# ISO_I2C.net
KiCad netlist of a schematic drawn in Altium Designer
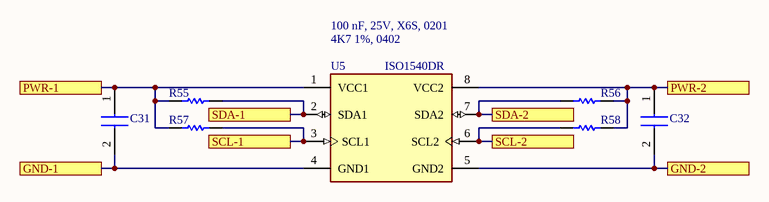
[diagram p0: ISO_I2C.SchDoc]

(export (version "E")
  (design (tool "Eeschema 10.0.6"))
  (components
    (comp (ref "C31")
      (value "100 nF, 25V, X6S, 0201")
      (footprint "SamacSys:CAPC0603X33N")
      (description "Capacitor")
      (fields
        (field (name "MANUFACTURER_PART_NUMBER") "GRM033C81E104KE14D")
        (field (name "MOUSER PART NUMBER") "81-GRM33C81E104KE14D")
      )
      (libsource (lib "*") (part "GRM033C81E104KE14D"))
    )
    (comp (ref "C32")
      (value "100 nF, 25V, X6S, 0201")
      (footprint "SamacSys:CAPC0603X33N")
      (description "Capacitor")
      (fields
        (field (name "MANUFACTURER_PART_NUMBER") "GRM033C81E104KE14D")
        (field (name "MOUSER PART NUMBER") "81-GRM33C81E104KE14D")
      )
      (libsource (lib "*") (part "GRM033C81E104KE14D"))
    )
    (comp (ref "R55")
      (value "4K7 1%, 0402")
      (footprint "RESC1005X40X25LL05T05")
      (description "Chip Resistor, 4.7 KOhm, +/- 1%, 0.1 W, -55 to 155 degC, 0402 (1005 Metric), RoHS, Tape and Reel")
      (fields (field (name "TOLERANCE") "1%") (field (name "PARTNUMBER") "ERJ-2RKF4701X"))
      (libsource (lib "Altium Content Vault") (part "RES-2"))
    )
    (comp (ref "R56")
      (value "4K7 1%, 0402")
      (footprint "RESC1005X40X25LL05T05")
      (description "Chip Resistor, 4.7 KOhm, +/- 1%, 0.1 W, -55 to 155 degC, 0402 (1005 Metric), RoHS, Tape and Reel")
      (fields (field (name "TOLERANCE") "1%") (field (name "PARTNUMBER") "ERJ-2RKF4701X"))
      (libsource (lib "Altium Content Vault") (part "RES-2"))
    )
    (comp (ref "R57")
      (value "4K7 1%, 0402")
      (footprint "RESC1005X40X25LL05T05")
      (description "Chip Resistor, 4.7 KOhm, +/- 1%, 0.1 W, -55 to 155 degC, 0402 (1005 Metric), RoHS, Tape and Reel")
      (fields (field (name "TOLERANCE") "1%") (field (name "PARTNUMBER") "ERJ-2RKF4701X"))
      (libsource (lib "Altium Content Vault") (part "RES-2"))
    )
    (comp (ref "R58")
      (value "4K7 1%, 0402")
      (footprint "RESC1005X40X25LL05T05")
      (description "Chip Resistor, 4.7 KOhm, +/- 1%, 0.1 W, -55 to 155 degC, 0402 (1005 Metric), RoHS, Tape and Reel")
      (fields (field (name "TOLERANCE") "1%") (field (name "PARTNUMBER") "ERJ-2RKF4701X"))
      (libsource (lib "Altium Content Vault") (part "RES-2"))
    )
    (comp (ref "U5")
      (value "ISO1540DR")
      (footprint "FP-D0008A-MFG")
      (description "DGTL ISO 2.5KV 2CH I2C 8SOIC")
      (fields
        (field (name "OCTOPART") "https://octopart.com/iso1540dr-texas+instruments-24334113")
        (field (name "MANUFACTURER") "Texas Instruments")
      )
      (libsource (lib "Altium Content Vault") (part "d824faccee5d143ad01692c0ddd1d85"))
    )
  )
  (nets
    (net (code "1") (name "/GND-1") (class "Default")
      (node (ref "C31") (pin "2") (pinfunction "2_2") (pintype "passive"))
      (node (ref "U5") (pin "4") (pinfunction "GND1_4") (pintype "power_in"))
    )
    (net (code "2") (name "/GND-2") (class "Default")
      (node (ref "C32") (pin "2") (pinfunction "2_2") (pintype "passive"))
      (node (ref "U5") (pin "5") (pinfunction "GND2_5") (pintype "power_in"))
    )
    (net (code "3") (name "/PWR-1") (class "Default")
      (node (ref "C31") (pin "1") (pinfunction "1_1") (pintype "passive"))
      (node (ref "R55") (pin "2") (pinfunction "2_2") (pintype "passive"))
      (node (ref "R57") (pin "2") (pinfunction "2_2") (pintype "passive"))
      (node (ref "U5") (pin "1") (pinfunction "VCC1_1") (pintype "power_in"))
    )
    (net (code "4") (name "/PWR-2") (class "Default")
      (node (ref "C32") (pin "1") (pinfunction "1_1") (pintype "passive"))
      (node (ref "R56") (pin "1") (pinfunction "1_1") (pintype "passive"))
      (node (ref "R58") (pin "1") (pinfunction "1_1") (pintype "passive"))
      (node (ref "U5") (pin "8") (pinfunction "VCC2_8") (pintype "power_in"))
    )
    (net (code "5") (name "/SCL-1") (class "Default")
      (node (ref "R57") (pin "1") (pinfunction "1_1") (pintype "passive"))
      (node (ref "U5") (pin "3") (pinfunction "SCL1_3") (pintype "input"))
    )
    (net (code "6") (name "/SCL-2") (class "Default")
      (node (ref "R58") (pin "2") (pinfunction "2_2") (pintype "passive"))
      (node (ref "U5") (pin "6") (pinfunction "SCL2_6") (pintype "input"))
    )
    (net (code "7") (name "/SDA-1") (class "Default")
      (node (ref "R55") (pin "1") (pinfunction "1_1") (pintype "passive"))
      (node (ref "U5") (pin "2") (pinfunction "SDA1_2") (pintype "bidirectional"))
    )
    (net (code "8") (name "/SDA-2") (class "Default")
      (node (ref "R56") (pin "2") (pinfunction "2_2") (pintype "passive"))
      (node (ref "U5") (pin "7") (pinfunction "SDA2_7") (pintype "bidirectional"))
    )
  )
)
